# uv.net
KiCad netlist of a schematic drawn in Altium Designer
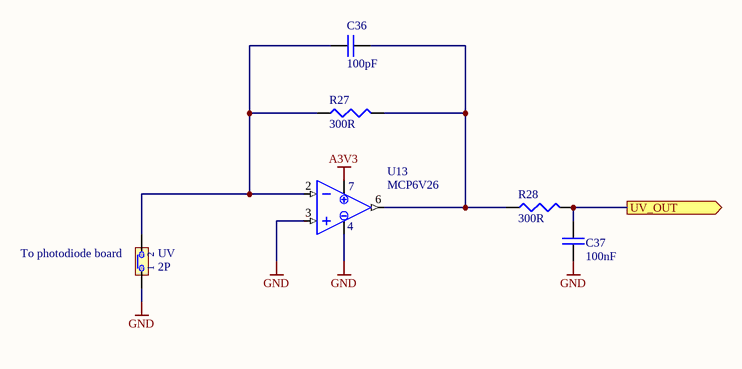
[diagram p0: uv.SchDoc]

(export (version "E")
  (design (tool "Eeschema 10.0.6"))
  (components
    (comp (ref "C36")
      (value "100pF")
      (footprint "0603")
      (description "Capacitor")
      (fields (field (name "OWNER") "Nuno Brum"))
      (libsource (lib "Alcetronics_Devices") (part "CAP"))
    )
    (comp (ref "C37")
      (value "100nF")
      (footprint "0603")
      (description "Capacitor")
      (fields (field (name "OWNER") "Nuno Brum"))
      (libsource (lib "Alcetronics_Devices") (part "CAP"))
    )
    (comp (ref "R27")
      (value "300R")
      (footprint "0603")
      (description "Resistor")
      (fields (field (name "OWNER") "Nuno Brum"))
      (libsource (lib "Alcetronics_Devices") (part "RES"))
    )
    (comp (ref "R28")
      (value "300R")
      (footprint "0603")
      (description "Resistor")
      (fields (field (name "OWNER") "Nuno Brum"))
      (libsource (lib "Alcetronics_Devices") (part "RES"))
    )
    (comp (ref "U13")
      (value "MCP6V26")
      (footprint "SOIC-8")
      (description "Low-Offset Opamp")
      (libsource (lib "Alcetronics_IC") (part "MCP6V26"))
    )
    (comp (ref "UV")
      (value "2P")
      (footprint "SIP-2")
      (description "2-pin Jumper")
      (fields (field (name "OWNER") "Nuno Brum"))
      (libsource (lib "Alcetronics_EM") (part "JMP2"))
    )
  )
  (nets
    (net (code "1") (name "/UV_OUT") (class "Default")
      (node (ref "C37") (pin "2") (pinfunction "2_2") (pintype "passive"))
      (node (ref "R28") (pin "2") (pinfunction "2_2") (pintype "passive"))
    )
    (net (code "2") (name "A3V3") (class "Default")
      (node (ref "U13") (pin "7") (pinfunction "VDD_7") (pintype "power_in"))
    )
    (net (code "3") (name "GND") (class "Default")
      (node (ref "C37") (pin "1") (pinfunction "1_1") (pintype "passive"))
      (node (ref "U13") (pin "3") (pinfunction "INP_3") (pintype "input"))
      (node (ref "U13") (pin "4") (pinfunction "VSS_4") (pintype "power_in"))
      (node (ref "UV") (pin "1") (pinfunction "1_1") (pintype "passive"))
    )
    (net (code "4") (name "Net-(U13-INN)") (class "Default")
      (node (ref "C36") (pin "1") (pinfunction "1_1") (pintype "passive"))
      (node (ref "R27") (pin "1") (pinfunction "1_1") (pintype "passive"))
      (node (ref "U13") (pin "2") (pinfunction "INN_2") (pintype "input"))
      (node (ref "UV") (pin "2") (pinfunction "2_2") (pintype "passive"))
    )
    (net (code "5") (name "Net-(U13-VOUT)") (class "Default")
      (node (ref "C36") (pin "2") (pinfunction "2_2") (pintype "passive"))
      (node (ref "R27") (pin "2") (pinfunction "2_2") (pintype "passive"))
      (node (ref "R28") (pin "1") (pinfunction "1_1") (pintype "passive"))
      (node (ref "U13") (pin "6") (pinfunction "VOUT_6") (pintype "output"))
    )
  )
)
